# BUOI13.net
KiCad netlist of a schematic drawn in Altium Designer
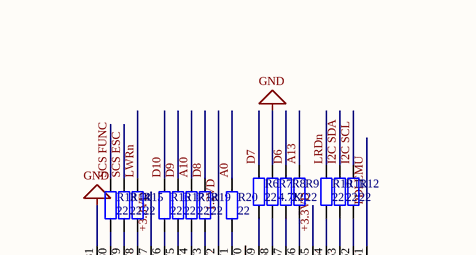
[diagram p0: BUOI13.SchDoc, top left]
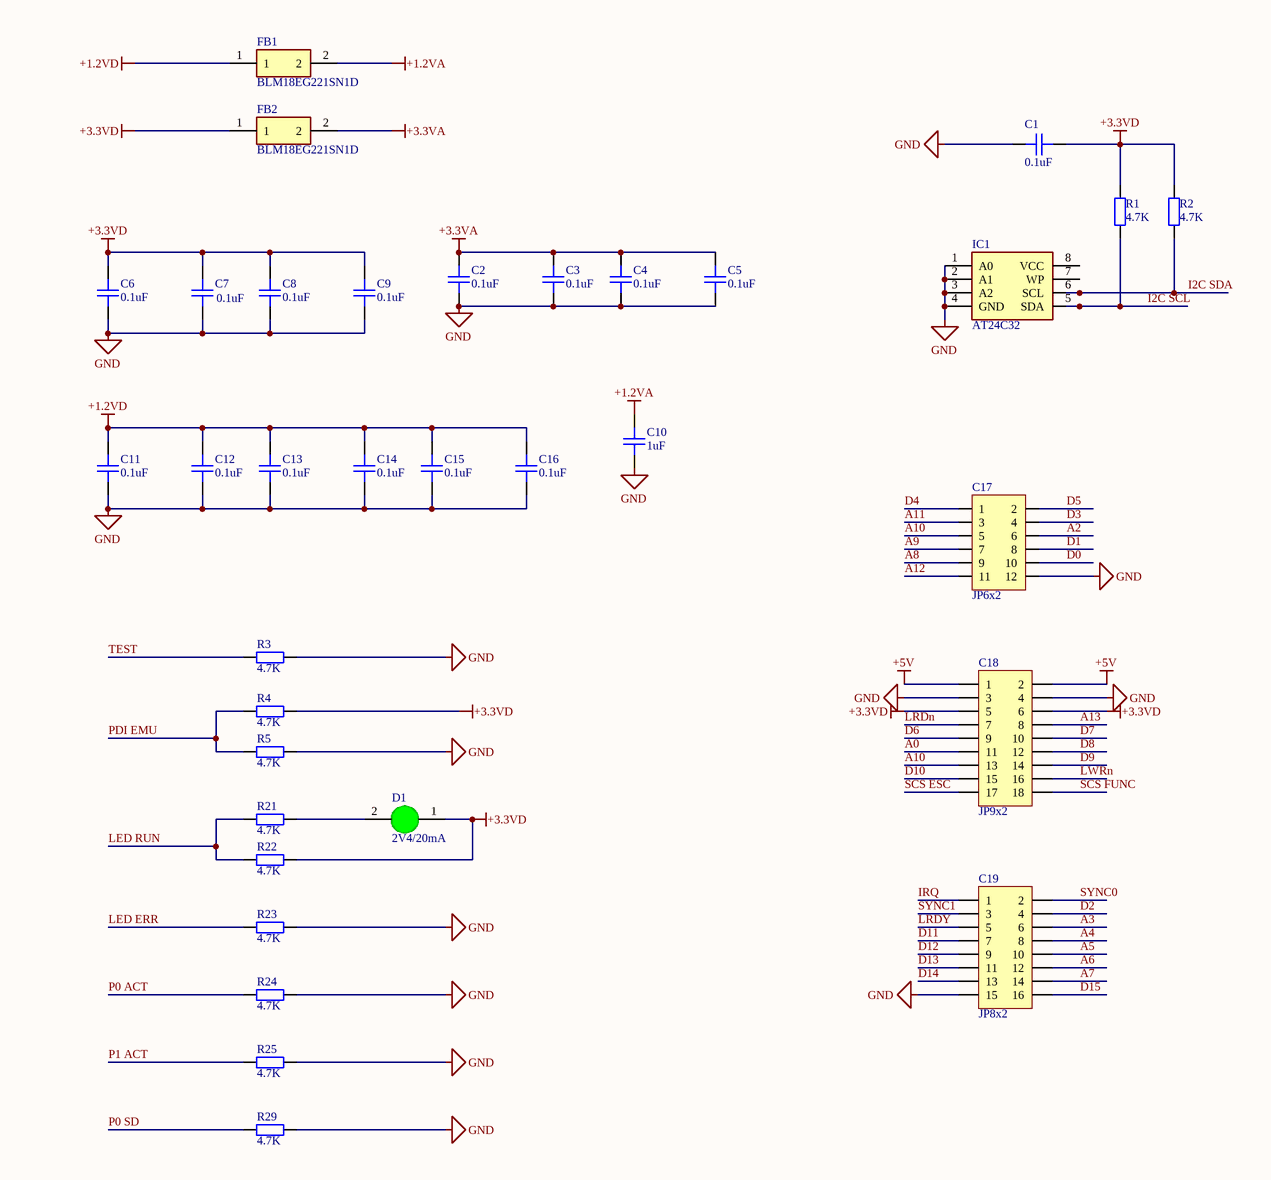
[diagram p1: BUOI13.SchDoc, top right]
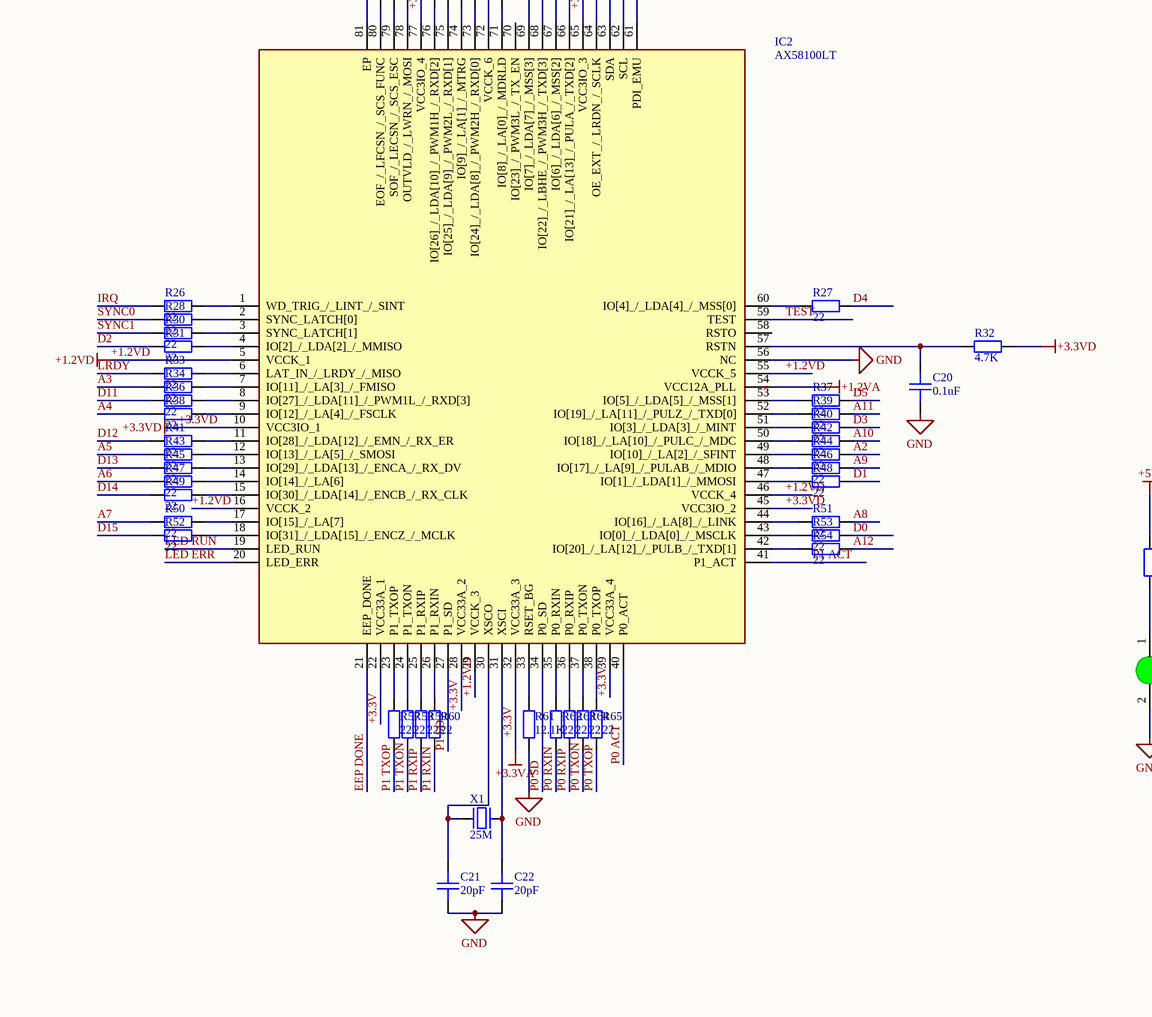
[diagram p2: BUOI13.SchDoc, bottom left]
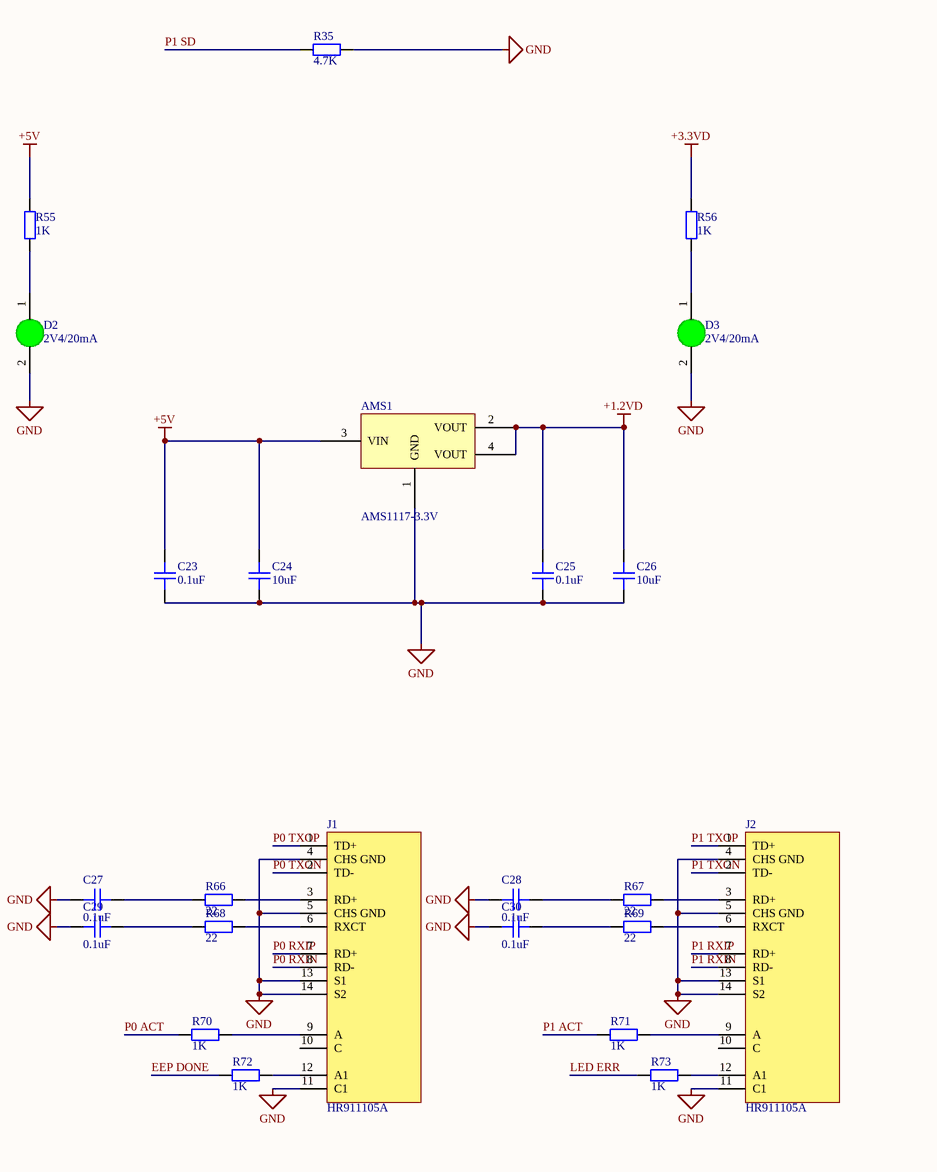
[diagram p3: BUOI13.SchDoc, bottom right]

(export (version "E")
  (design (tool "Eeschema 10.0.6"))
  (components
    (comp (ref "AMS1")
      (value "AMS1117-3.3V")
      (footprint "SOT223-4N")
      (description "Dán")
      (libsource (lib "THU VIEN SCH") (part "AMS1117"))
    )
    (comp (ref "C1")
      (value "0.1uF")
      (footprint "CAPC-0603 (1608)")
      (description "CAP CER 33pF 50V 5%  0603")
      (fields (field (name "MPN") "CL10C330JB8NNNC, 0603N330J500CT"))
      (libsource (lib "BYTECH_HW_LIB_2019 (1)") (part "0603N330J500CT"))
    )
    (comp (ref "C2")
      (value "0.1uF")
      (footprint "CAPC-0603 (1608)")
      (description "CAP CER 33pF 50V 5%  0603")
      (fields (field (name "MPN") "CL10C330JB8NNNC, 0603N330J500CT"))
      (libsource (lib "BYTECH_HW_LIB_2019 (1)") (part "0603N330J500CT"))
    )
    (comp (ref "C3")
      (value "0.1uF")
      (footprint "CAPC-0603 (1608)")
      (description "CAP CER 33pF 50V 5%  0603")
      (fields (field (name "MPN") "CL10C330JB8NNNC, 0603N330J500CT"))
      (libsource (lib "BYTECH_HW_LIB_2019 (1)") (part "0603N330J500CT"))
    )
    (comp (ref "C4")
      (value "0.1uF")
      (footprint "CAPC-0603 (1608)")
      (description "CAP CER 33pF 50V 5%  0603")
      (fields (field (name "MPN") "CL10C330JB8NNNC, 0603N330J500CT"))
      (libsource (lib "BYTECH_HW_LIB_2019 (1)") (part "0603N330J500CT"))
    )
    (comp (ref "C5")
      (value "0.1uF")
      (footprint "CAPC-0603 (1608)")
      (description "CAP CER 33pF 50V 5%  0603")
      (fields (field (name "MPN") "CL10C330JB8NNNC, 0603N330J500CT"))
      (libsource (lib "BYTECH_HW_LIB_2019 (1)") (part "0603N330J500CT"))
    )
    (comp (ref "C6")
      (value "0.1uF")
      (footprint "CAPC-0603 (1608)")
      (description "CAP CER 33pF 50V 5%  0603")
      (fields (field (name "MPN") "CL10C330JB8NNNC, 0603N330J500CT"))
      (libsource (lib "BYTECH_HW_LIB_2019 (1)") (part "0603N330J500CT"))
    )
    (comp (ref "C7")
      (value "0.1uF")
      (footprint "CAPC-0603 (1608)")
      (description "CAP CER 33pF 50V 5%  0603")
      (fields (field (name "MPN") "CL10C330JB8NNNC, 0603N330J500CT"))
      (libsource (lib "BYTECH_HW_LIB_2019 (1)") (part "0603N330J500CT"))
    )
    (comp (ref "C8")
      (value "0.1uF")
      (footprint "CAPC-0603 (1608)")
      (description "CAP CER 33pF 50V 5%  0603")
      (fields (field (name "MPN") "CL10C330JB8NNNC, 0603N330J500CT"))
      (libsource (lib "BYTECH_HW_LIB_2019 (1)") (part "0603N330J500CT"))
    )
    (comp (ref "C9")
      (value "0.1uF")
      (footprint "CAPC-0603 (1608)")
      (description "CAP CER 33pF 50V 5%  0603")
      (fields (field (name "MPN") "CL10C330JB8NNNC, 0603N330J500CT"))
      (libsource (lib "BYTECH_HW_LIB_2019 (1)") (part "0603N330J500CT"))
    )
    (comp (ref "C10")
      (value "1uF")
      (footprint "CAPC-0603 (1608)")
      (description "CAP CER 33pF 50V 5%  0603")
      (fields (field (name "MPN") "CL10C330JB8NNNC, 0603N330J500CT"))
      (libsource (lib "BYTECH_HW_LIB_2019 (1)") (part "0603N330J500CT"))
    )
    (comp (ref "C11")
      (value "0.1uF")
      (footprint "CAPC-0603 (1608)")
      (description "CAP CER 33pF 50V 5%  0603")
      (fields (field (name "MPN") "CL10C330JB8NNNC, 0603N330J500CT"))
      (libsource (lib "BYTECH_HW_LIB_2019 (1)") (part "0603N330J500CT"))
    )
    (comp (ref "C12")
      (value "0.1uF")
      (footprint "CAPC-0603 (1608)")
      (description "CAP CER 33pF 50V 5%  0603")
      (fields (field (name "MPN") "CL10C330JB8NNNC, 0603N330J500CT"))
      (libsource (lib "BYTECH_HW_LIB_2019 (1)") (part "0603N330J500CT"))
    )
    (comp (ref "C13")
      (value "0.1uF")
      (footprint "CAPC-0603 (1608)")
      (description "CAP CER 33pF 50V 5%  0603")
      (fields (field (name "MPN") "CL10C330JB8NNNC, 0603N330J500CT"))
      (libsource (lib "BYTECH_HW_LIB_2019 (1)") (part "0603N330J500CT"))
    )
    (comp (ref "C14")
      (value "0.1uF")
      (footprint "CAPC-0603 (1608)")
      (description "CAP CER 33pF 50V 5%  0603")
      (fields (field (name "MPN") "CL10C330JB8NNNC, 0603N330J500CT"))
      (libsource (lib "BYTECH_HW_LIB_2019 (1)") (part "0603N330J500CT"))
    )
    (comp (ref "C15")
      (value "0.1uF")
      (footprint "CAPC-0603 (1608)")
      (description "CAP CER 33pF 50V 5%  0603")
      (fields (field (name "MPN") "CL10C330JB8NNNC, 0603N330J500CT"))
      (libsource (lib "BYTECH_HW_LIB_2019 (1)") (part "0603N330J500CT"))
    )
    (comp (ref "C16")
      (value "0.1uF")
      (footprint "CAPC-0603 (1608)")
      (description "CAP CER 33pF 50V 5%  0603")
      (fields (field (name "MPN") "CL10C330JB8NNNC, 0603N330J500CT"))
      (libsource (lib "BYTECH_HW_LIB_2019 (1)") (part "0603N330J500CT"))
    )
    (comp (ref "C17")
      (value "JP6x2")
      (footprint "JP6-D2T")
      (description "WR-PHD 2.54 mm Dual Socket Header")
      (fields
        (field (name "MANUFACTURER") "Würth Elektronik eiSos GmbH")
        (field (name "PARTNO") "61301221821")
        (field (name "CREATED BY") "Karrer Zheng")
      )
      (libsource (lib "TechMT.VN_Lib_Project v2") (part "JP6x2"))
    )
    (comp (ref "C18")
      (value "JP9x2")
      (footprint "JP9-D2T")
      (description "WR-PHD 2.54 mm Dual Socket Header")
      (fields
        (field (name "MANUFACTURER") "Würth Elektronik eiSos GmbH")
        (field (name "PARTNO") "61301821821")
        (field (name "CREATED BY") "Karrer Zheng")
      )
      (libsource (lib "TechMT.VN_Lib_Project v2") (part "JP9x2"))
    )
    (comp (ref "C19")
      (value "JP8x2")
      (footprint "JP8-D2T")
      (description "WR-PHD 2.54 mm Dual Socket Header")
      (fields
        (field (name "MANUFACTURER") "Würth Elektronik eiSos GmbH")
        (field (name "PARTNO") "61301621821")
        (field (name "CREATED BY") "Karrer Zheng")
      )
      (libsource (lib "TechMT.VN_Lib_Project v2") (part "JP8x2"))
    )
    (comp (ref "C20")
      (value "0.1uF")
      (footprint "CAPC-0603 (1608)")
      (description "CAP CER 33pF 50V 5%  0603")
      (fields (field (name "MPN") "CL10C330JB8NNNC, 0603N330J500CT"))
      (libsource (lib "BYTECH_HW_LIB_2019 (1)") (part "0603N330J500CT"))
    )
    (comp (ref "C21")
      (value "20pF")
      (footprint "CAPC-0603 (1608)")
      (description "CAP CER 33pF 50V 5%  0603")
      (fields (field (name "MPN") "CL10C330JB8NNNC, 0603N330J500CT"))
      (libsource (lib "BYTECH_HW_LIB_2019 (1)") (part "0603N330J500CT"))
    )
    (comp (ref "C22")
      (value "20pF")
      (footprint "CAPC-0603 (1608)")
      (description "CAP CER 33pF 50V 5%  0603")
      (fields (field (name "MPN") "CL10C330JB8NNNC, 0603N330J500CT"))
      (libsource (lib "BYTECH_HW_LIB_2019 (1)") (part "0603N330J500CT"))
    )
    (comp (ref "C23")
      (value "0.1uF")
      (footprint "CAPC-0603 (1608)")
      (description "CAP CER 33pF 50V 5%  0603")
      (fields (field (name "MPN") "CL10C330JB8NNNC, 0603N330J500CT"))
      (libsource (lib "BYTECH_HW_LIB_2019 (1)") (part "0603N330J500CT"))
    )
    (comp (ref "C24")
      (value "10uF")
      (footprint "CAPC-0603 (1608)")
      (description "CAP CER 33pF 50V 5%  0603")
      (fields (field (name "MPN") "CL10C330JB8NNNC, 0603N330J500CT"))
      (libsource (lib "BYTECH_HW_LIB_2019 (1)") (part "0603N330J500CT"))
    )
    (comp (ref "C25")
      (value "0.1uF")
      (footprint "CAPC-0603 (1608)")
      (description "CAP CER 33pF 50V 5%  0603")
      (fields (field (name "MPN") "CL10C330JB8NNNC, 0603N330J500CT"))
      (libsource (lib "BYTECH_HW_LIB_2019 (1)") (part "0603N330J500CT"))
    )
    (comp (ref "C26")
      (value "10uF")
      (footprint "CAPC-0603 (1608)")
      (description "CAP CER 33pF 50V 5%  0603")
      (fields (field (name "MPN") "CL10C330JB8NNNC, 0603N330J500CT"))
      (libsource (lib "BYTECH_HW_LIB_2019 (1)") (part "0603N330J500CT"))
    )
    (comp (ref "C27")
      (value "0.1uF")
      (footprint "CAPC-0603 (1608)")
      (description "CAP CER 33pF 50V 5%  0603")
      (fields (field (name "MPN") "CL10C330JB8NNNC, 0603N330J500CT"))
      (libsource (lib "BYTECH_HW_LIB_2019 (1)") (part "0603N330J500CT"))
    )
    (comp (ref "C28")
      (value "0.1uF")
      (footprint "CAPC-0603 (1608)")
      (description "CAP CER 33pF 50V 5%  0603")
      (fields (field (name "MPN") "CL10C330JB8NNNC, 0603N330J500CT"))
      (libsource (lib "BYTECH_HW_LIB_2019 (1)") (part "0603N330J500CT"))
    )
    (comp (ref "C29")
      (value "0.1uF")
      (footprint "CAPC-0603 (1608)")
      (description "CAP CER 33pF 50V 5%  0603")
      (fields (field (name "MPN") "CL10C330JB8NNNC, 0603N330J500CT"))
      (libsource (lib "BYTECH_HW_LIB_2019 (1)") (part "0603N330J500CT"))
    )
    (comp (ref "C30")
      (value "0.1uF")
      (footprint "CAPC-0603 (1608)")
      (description "CAP CER 33pF 50V 5%  0603")
      (fields (field (name "MPN") "CL10C330JB8NNNC, 0603N330J500CT"))
      (libsource (lib "BYTECH_HW_LIB_2019 (1)") (part "0603N330J500CT"))
    )
    (comp (ref "D1")
      (value "2V4/20mA")
      (footprint "LED_0805_GREEN")
      (description "LED GREEN CLEAR 2V4 20mA 0805 SMD")
      (fields (field (name "MPN") "17-21/G6C-FM1N2B/3T"))
      (libsource (lib "BYTECH_HW_LIB_2019 (1)") (part "17-21/G6C-FM1N2B/3T"))
    )
    (comp (ref "D2")
      (value "2V4/20mA")
      (footprint "LED_0805_GREEN")
      (description "LED GREEN CLEAR 2V4 20mA 0805 SMD")
      (fields (field (name "MPN") "17-21/G6C-FM1N2B/3T"))
      (libsource (lib "BYTECH_HW_LIB_2019 (1)") (part "17-21/G6C-FM1N2B/3T"))
    )
    (comp (ref "D3")
      (value "2V4/20mA")
      (footprint "LED_0805_GREEN")
      (description "LED GREEN CLEAR 2V4 20mA 0805 SMD")
      (fields (field (name "MPN") "17-21/G6C-FM1N2B/3T"))
      (libsource (lib "BYTECH_HW_LIB_2019 (1)") (part "17-21/G6C-FM1N2B/3T"))
    )
    (comp (ref "FB1")
      (value "BLM18EG221SN1D")
      (footprint "BLM18EG121SH1D")
      (description "Ferrite Bead")
      (fields (field (name "MOUSER PART NUMBER") "81-BLM18EG221SN1D"))
      (libsource (lib "BLM") (part "BLM18EG221SN1D"))
    )
    (comp (ref "FB2")
      (value "BLM18EG221SN1D")
      (footprint "BLM18EG121SH1D")
      (description "Ferrite Bead")
      (fields (field (name "MOUSER PART NUMBER") "81-BLM18EG221SN1D"))
      (libsource (lib "BLM") (part "BLM18EG221SN1D"))
    )
    (comp (ref "IC1")
      (value "AT24C32")
      (footprint "SOIC127P600X175-8N")
      (description "Integrated Circuit")
      (libsource (lib "SamacSys") (part "AT24C32"))
    )
    (comp (ref "IC2")
      (value "AX58100LT")
      (footprint "QFP40P1200X1200X160-81N")
      (description "Integrated Circuit")
      (libsource (lib "BLM") (part "AX58100LT"))
    )
    (comp (ref "J1")
      (value "HR911105A")
      (footprint "HR911105A")
      (description "Hanrun HR911105A RJ-45 Connector")
      (fields (field (name "MFR") "HanRun"))
      (libsource (lib "BYTECH_HW_LIB_2019 (1)") (part "HR911105A"))
    )
    (comp (ref "J2")
      (value "HR911105A")
      (footprint "HR911105A")
      (description "Hanrun HR911105A RJ-45 Connector")
      (fields (field (name "MFR") "HanRun"))
      (libsource (lib "BYTECH_HW_LIB_2019 (1)") (part "HR911105A"))
    )
    (comp (ref "R1")
      (value "4.7K")
      (footprint "RESC-0603 (1608)")
      (description "RES SMD 13K OHM 1% 1/10W 0603")
      (fields (field (name "MPN") "AC0603FR-0713KL"))
      (libsource (lib "") (part "AC0603FR-0713KL_2"))
    )
    (comp (ref "R2")
      (value "4.7K")
      (footprint "RESC-0603 (1608)")
      (description "RES SMD 13K OHM 1% 1/10W 0603")
      (fields (field (name "MPN") "AC0603FR-0713KL"))
      (libsource (lib "") (part "AC0603FR-0713KL_2"))
    )
    (comp (ref "R3")
      (value "4.7K")
      (footprint "RESC-0603 (1608)")
      (description "RES SMD 13K OHM 1% 1/10W 0603")
      (fields (field (name "MPN") "AC0603FR-0713KL"))
      (libsource (lib "") (part "AC0603FR-0713KL_3"))
    )
    (comp (ref "R4")
      (value "4.7K")
      (footprint "RESC-0603 (1608)")
      (description "RES SMD 13K OHM 1% 1/10W 0603")
      (fields (field (name "MPN") "AC0603FR-0713KL"))
      (libsource (lib "") (part "AC0603FR-0713KL_3"))
    )
    (comp (ref "R5")
      (value "4.7K")
      (footprint "RESC-0603 (1608)")
      (description "RES SMD 13K OHM 1% 1/10W 0603")
      (fields (field (name "MPN") "AC0603FR-0713KL"))
      (libsource (lib "") (part "AC0603FR-0713KL_3"))
    )
    (comp (ref "R6")
      (value "22")
      (footprint "RESC-0603 (1608)")
      (description "RES SMD 13K OHM 1% 1/10W 0603")
      (fields (field (name "MPN") "AC0603FR-0713KL"))
      (libsource (lib "") (part "AC0603FR-0713KL_2"))
    )
    (comp (ref "R7")
      (value "4.7K")
      (footprint "RESC-0603 (1608)")
      (description "RES SMD 13K OHM 1% 1/10W 0603")
      (fields (field (name "MPN") "AC0603FR-0713KL"))
      (libsource (lib "") (part "AC0603FR-0713KL_2"))
    )
    (comp (ref "R8")
      (value "22")
      (footprint "RESC-0603 (1608)")
      (description "RES SMD 13K OHM 1% 1/10W 0603")
      (fields (field (name "MPN") "AC0603FR-0713KL"))
      (libsource (lib "") (part "AC0603FR-0713KL_2"))
    )
    (comp (ref "R9")
      (value "22")
      (footprint "RESC-0603 (1608)")
      (description "RES SMD 13K OHM 1% 1/10W 0603")
      (fields (field (name "MPN") "AC0603FR-0713KL"))
      (libsource (lib "BYTECH_HW_LIB_2019 (1)") (part "AC0603FR-0713KL"))
    )
    (comp (ref "R10")
      (value "22")
      (footprint "RESC-0603 (1608)")
      (description "RES SMD 13K OHM 1% 1/10W 0603")
      (fields (field (name "MPN") "AC0603FR-0713KL"))
      (libsource (lib "BYTECH_HW_LIB_2019 (1)") (part "AC0603FR-0713KL"))
    )
    (comp (ref "R11")
      (value "22")
      (footprint "RESC-0603 (1608)")
      (description "RES SMD 13K OHM 1% 1/10W 0603")
      (fields (field (name "MPN") "AC0603FR-0713KL"))
      (libsource (lib "BYTECH_HW_LIB_2019 (1)") (part "AC0603FR-0713KL"))
    )
    (comp (ref "R12")
      (value "22")
      (footprint "RESC-0603 (1608)")
      (description "RES SMD 13K OHM 1% 1/10W 0603")
      (fields (field (name "MPN") "AC0603FR-0713KL"))
      (libsource (lib "BYTECH_HW_LIB_2019 (1)") (part "AC0603FR-0713KL"))
    )
    (comp (ref "R13")
      (value "22")
      (footprint "RESC-0603 (1608)")
      (description "RES SMD 13K OHM 1% 1/10W 0603")
      (fields (field (name "MPN") "AC0603FR-0713KL"))
      (libsource (lib "BYTECH_HW_LIB_2019 (1)") (part "AC0603FR-0713KL"))
    )
    (comp (ref "R14")
      (value "22")
      (footprint "RESC-0603 (1608)")
      (description "RES SMD 13K OHM 1% 1/10W 0603")
      (fields (field (name "MPN") "AC0603FR-0713KL"))
      (libsource (lib "BYTECH_HW_LIB_2019 (1)") (part "AC0603FR-0713KL"))
    )
    (comp (ref "R15")
      (value "22")
      (footprint "RESC-0603 (1608)")
      (description "RES SMD 13K OHM 1% 1/10W 0603")
      (fields (field (name "MPN") "AC0603FR-0713KL"))
      (libsource (lib "BYTECH_HW_LIB_2019 (1)") (part "AC0603FR-0713KL"))
    )
    (comp (ref "R16")
      (value "22")
      (footprint "RESC-0603 (1608)")
      (description "RES SMD 13K OHM 1% 1/10W 0603")
      (fields (field (name "MPN") "AC0603FR-0713KL"))
      (libsource (lib "BYTECH_HW_LIB_2019 (1)") (part "AC0603FR-0713KL"))
    )
    (comp (ref "R17")
      (value "22")
      (footprint "RESC-0603 (1608)")
      (description "RES SMD 13K OHM 1% 1/10W 0603")
      (fields (field (name "MPN") "AC0603FR-0713KL"))
      (libsource (lib "BYTECH_HW_LIB_2019 (1)") (part "AC0603FR-0713KL"))
    )
    (comp (ref "R18")
      (value "22")
      (footprint "RESC-0603 (1608)")
      (description "RES SMD 13K OHM 1% 1/10W 0603")
      (fields (field (name "MPN") "AC0603FR-0713KL"))
      (libsource (lib "") (part "AC0603FR-0713KL_2"))
    )
    (comp (ref "R19")
      (value "22")
      (footprint "RESC-0603 (1608)")
      (description "RES SMD 13K OHM 1% 1/10W 0603")
      (fields (field (name "MPN") "AC0603FR-0713KL"))
      (libsource (lib "BYTECH_HW_LIB_2019 (1)") (part "AC0603FR-0713KL"))
    )
    (comp (ref "R20")
      (value "22")
      (footprint "RESC-0603 (1608)")
      (description "RES SMD 13K OHM 1% 1/10W 0603")
      (fields (field (name "MPN") "AC0603FR-0713KL"))
      (libsource (lib "") (part "AC0603FR-0713KL_2"))
    )
    (comp (ref "R21")
      (value "4.7K")
      (footprint "RESC-0603 (1608)")
      (description "RES SMD 13K OHM 1% 1/10W 0603")
      (fields (field (name "MPN") "AC0603FR-0713KL"))
      (libsource (lib "") (part "AC0603FR-0713KL_3"))
    )
    (comp (ref "R22")
      (value "4.7K")
      (footprint "RESC-0603 (1608)")
      (description "RES SMD 13K OHM 1% 1/10W 0603")
      (fields (field (name "MPN") "AC0603FR-0713KL"))
      (libsource (lib "") (part "AC0603FR-0713KL_3"))
    )
    (comp (ref "R23")
      (value "4.7K")
      (footprint "RESC-0603 (1608)")
      (description "RES SMD 13K OHM 1% 1/10W 0603")
      (fields (field (name "MPN") "AC0603FR-0713KL"))
      (libsource (lib "") (part "AC0603FR-0713KL_3"))
    )
    (comp (ref "R24")
      (value "4.7K")
      (footprint "RESC-0603 (1608)")
      (description "RES SMD 13K OHM 1% 1/10W 0603")
      (fields (field (name "MPN") "AC0603FR-0713KL"))
      (libsource (lib "") (part "AC0603FR-0713KL_3"))
    )
    (comp (ref "R25")
      (value "4.7K")
      (footprint "RESC-0603 (1608)")
      (description "RES SMD 13K OHM 1% 1/10W 0603")
      (fields (field (name "MPN") "AC0603FR-0713KL"))
      (libsource (lib "") (part "AC0603FR-0713KL_3"))
    )
    (comp (ref "R26")
      (value "22")
      (footprint "RESC-0603 (1608)")
      (description "RES SMD 13K OHM 1% 1/10W 0603")
      (fields (field (name "MPN") "AC0603FR-0713KL"))
      (libsource (lib "") (part "AC0603FR-0713KL_1"))
    )
    (comp (ref "R27")
      (value "22")
      (footprint "RESC-0603 (1608)")
      (description "RES SMD 13K OHM 1% 1/10W 0603")
      (fields (field (name "MPN") "AC0603FR-0713KL"))
      (libsource (lib "") (part "AC0603FR-0713KL_1"))
    )
    (comp (ref "R28")
      (value "22")
      (footprint "RESC-0603 (1608)")
      (description "RES SMD 13K OHM 1% 1/10W 0603")
      (fields (field (name "MPN") "AC0603FR-0713KL"))
      (libsource (lib "") (part "AC0603FR-0713KL_1"))
    )
    (comp (ref "R29")
      (value "4.7K")
      (footprint "RESC-0603 (1608)")
      (description "RES SMD 13K OHM 1% 1/10W 0603")
      (fields (field (name "MPN") "AC0603FR-0713KL"))
      (libsource (lib "") (part "AC0603FR-0713KL_3"))
    )
    (comp (ref "R30")
      (value "22")
      (footprint "RESC-0603 (1608)")
      (description "RES SMD 13K OHM 1% 1/10W 0603")
      (fields (field (name "MPN") "AC0603FR-0713KL"))
      (libsource (lib "") (part "AC0603FR-0713KL_1"))
    )
    (comp (ref "R31")
      (value "22")
      (footprint "RESC-0603 (1608)")
      (description "RES SMD 13K OHM 1% 1/10W 0603")
      (fields (field (name "MPN") "AC0603FR-0713KL"))
      (libsource (lib "") (part "AC0603FR-0713KL_1"))
    )
    (comp (ref "R32")
      (value "4.7K")
      (footprint "RESC-0603 (1608)")
      (description "RES SMD 13K OHM 1% 1/10W 0603")
      (fields (field (name "MPN") "AC0603FR-0713KL"))
      (libsource (lib "") (part "AC0603FR-0713KL_1"))
    )
    (comp (ref "R33")
      (value "22")
      (footprint "RESC-0603 (1608)")
      (description "RES SMD 13K OHM 1% 1/10W 0603")
      (fields (field (name "MPN") "AC0603FR-0713KL"))
      (libsource (lib "") (part "AC0603FR-0713KL_1"))
    )
    (comp (ref "R34")
      (value "22")
      (footprint "RESC-0603 (1608)")
      (description "RES SMD 13K OHM 1% 1/10W 0603")
      (fields (field (name "MPN") "AC0603FR-0713KL"))
      (libsource (lib "") (part "AC0603FR-0713KL_1"))
    )
    (comp (ref "R35")
      (value "4.7K")
      (footprint "RESC-0603 (1608)")
      (description "RES SMD 13K OHM 1% 1/10W 0603")
      (fields (field (name "MPN") "AC0603FR-0713KL"))
      (libsource (lib "") (part "AC0603FR-0713KL_3"))
    )
    (comp (ref "R36")
      (value "22")
      (footprint "RESC-0603 (1608)")
      (description "RES SMD 13K OHM 1% 1/10W 0603")
      (fields (field (name "MPN") "AC0603FR-0713KL"))
      (libsource (lib "") (part "AC0603FR-0713KL_1"))
    )
    (comp (ref "R37")
      (value "22")
      (footprint "RESC-0603 (1608)")
      (description "RES SMD 13K OHM 1% 1/10W 0603")
      (fields (field (name "MPN") "AC0603FR-0713KL"))
      (libsource (lib "") (part "AC0603FR-0713KL_1"))
    )
    (comp (ref "R38")
      (value "22")
      (footprint "RESC-0603 (1608)")
      (description "RES SMD 13K OHM 1% 1/10W 0603")
      (fields (field (name "MPN") "AC0603FR-0713KL"))
      (libsource (lib "") (part "AC0603FR-0713KL_1"))
    )
    (comp (ref "R39")
      (value "22")
      (footprint "RESC-0603 (1608)")
      (description "RES SMD 13K OHM 1% 1/10W 0603")
      (fields (field (name "MPN") "AC0603FR-0713KL"))
      (libsource (lib "") (part "AC0603FR-0713KL_1"))
    )
    (comp (ref "R40")
      (value "22")
      (footprint "RESC-0603 (1608)")
      (description "RES SMD 13K OHM 1% 1/10W 0603")
      (fields (field (name "MPN") "AC0603FR-0713KL"))
      (libsource (lib "") (part "AC0603FR-0713KL_1"))
    )
    (comp (ref "R41")
      (value "22")
      (footprint "RESC-0603 (1608)")
      (description "RES SMD 13K OHM 1% 1/10W 0603")
      (fields (field (name "MPN") "AC0603FR-0713KL"))
      (libsource (lib "") (part "AC0603FR-0713KL_1"))
    )
    (comp (ref "R42")
      (value "22")
      (footprint "RESC-0603 (1608)")
      (description "RES SMD 13K OHM 1% 1/10W 0603")
      (fields (field (name "MPN") "AC0603FR-0713KL"))
      (libsource (lib "") (part "AC0603FR-0713KL_1"))
    )
    (comp (ref "R43")
      (value "22")
      (footprint "RESC-0603 (1608)")
      (description "RES SMD 13K OHM 1% 1/10W 0603")
      (fields (field (name "MPN") "AC0603FR-0713KL"))
      (libsource (lib "") (part "AC0603FR-0713KL_1"))
    )
    (comp (ref "R44")
      (value "22")
      (footprint "RESC-0603 (1608)")
      (description "RES SMD 13K OHM 1% 1/10W 0603")
      (fields (field (name "MPN") "AC0603FR-0713KL"))
      (libsource (lib "") (part "AC0603FR-0713KL_1"))
    )
    (comp (ref "R45")
      (value "22")
      (footprint "RESC-0603 (1608)")
      (description "RES SMD 13K OHM 1% 1/10W 0603")
      (fields (field (name "MPN") "AC0603FR-0713KL"))
      (libsource (lib "") (part "AC0603FR-0713KL_1"))
    )
    (comp (ref "R46")
      (value "22")
      (footprint "RESC-0603 (1608)")
      (description "RES SMD 13K OHM 1% 1/10W 0603")
      (fields (field (name "MPN") "AC0603FR-0713KL"))
      (libsource (lib "") (part "AC0603FR-0713KL_1"))
    )
    (comp (ref "R47")
      (value "22")
      (footprint "RESC-0603 (1608)")
      (description "RES SMD 13K OHM 1% 1/10W 0603")
      (fields (field (name "MPN") "AC0603FR-0713KL"))
      (libsource (lib "") (part "AC0603FR-0713KL_1"))
    )
    (comp (ref "R48")
      (value "22")
      (footprint "RESC-0603 (1608)")
      (description "RES SMD 13K OHM 1% 1/10W 0603")
      (fields (field (name "MPN") "AC0603FR-0713KL"))
      (libsource (lib "") (part "AC0603FR-0713KL_1"))
    )
    (comp (ref "R49")
      (value "22")
      (footprint "RESC-0603 (1608)")
      (description "RES SMD 13K OHM 1% 1/10W 0603")
      (fields (field (name "MPN") "AC0603FR-0713KL"))
      (libsource (lib "") (part "AC0603FR-0713KL_1"))
    )
    (comp (ref "R50")
      (value "22")
      (footprint "RESC-0603 (1608)")
      (description "RES SMD 13K OHM 1% 1/10W 0603")
      (fields (field (name "MPN") "AC0603FR-0713KL"))
      (libsource (lib "") (part "AC0603FR-0713KL_1"))
    )
    (comp (ref "R51")
      (value "22")
      (footprint "RESC-0603 (1608)")
      (description "RES SMD 13K OHM 1% 1/10W 0603")
      (fields (field (name "MPN") "AC0603FR-0713KL"))
      (libsource (lib "") (part "AC0603FR-0713KL_1"))
    )
    (comp (ref "R52")
      (value "22")
      (footprint "RESC-0603 (1608)")
      (description "RES SMD 13K OHM 1% 1/10W 0603")
      (fields (field (name "MPN") "AC0603FR-0713KL"))
      (libsource (lib "") (part "AC0603FR-0713KL_1"))
    )
    (comp (ref "R53")
      (value "22")
      (footprint "RESC-0603 (1608)")
      (description "RES SMD 13K OHM 1% 1/10W 0603")
      (fields (field (name "MPN") "AC0603FR-0713KL"))
      (libsource (lib "") (part "AC0603FR-0713KL_1"))
    )
    (comp (ref "R54")
      (value "22")
      (footprint "RESC-0603 (1608)")
      (description "RES SMD 13K OHM 1% 1/10W 0603")
      (fields (field (name "MPN") "AC0603FR-0713KL"))
      (libsource (lib "") (part "AC0603FR-0713KL_1"))
    )
    (comp (ref "R55")
      (value "1K")
      (footprint "RESC-0603 (1608)")
      (description "RES SMD 13K OHM 1% 1/10W 0603")
      (fields (field (name "MPN") "AC0603FR-0713KL"))
      (libsource (lib "") (part "AC0603FR-0713KL_2"))
    )
    (comp (ref "R56")
      (value "1K")
      (footprint "RESC-0603 (1608)")
      (description "RES SMD 13K OHM 1% 1/10W 0603")
      (fields (field (name "MPN") "AC0603FR-0713KL"))
      (libsource (lib "") (part "AC0603FR-0713KL_2"))
    )
    (comp (ref "R57")
      (value "22")
      (footprint "RESC-0603 (1608)")
      (description "RES SMD 13K OHM 1% 1/10W 0603")
      (fields (field (name "MPN") "AC0603FR-0713KL"))
      (libsource (lib "BYTECH_HW_LIB_2019 (1)") (part "AC0603FR-0713KL"))
    )
    (comp (ref "R58")
      (value "22")
      (footprint "RESC-0603 (1608)")
      (description "RES SMD 13K OHM 1% 1/10W 0603")
      (fields (field (name "MPN") "AC0603FR-0713KL"))
      (libsource (lib "BYTECH_HW_LIB_2019 (1)") (part "AC0603FR-0713KL"))
    )
    (comp (ref "R59")
      (value "22")
      (footprint "RESC-0603 (1608)")
      (description "RES SMD 13K OHM 1% 1/10W 0603")
      (fields (field (name "MPN") "AC0603FR-0713KL"))
      (libsource (lib "BYTECH_HW_LIB_2019 (1)") (part "AC0603FR-0713KL"))
    )
    (comp (ref "R60")
      (value "22")
      (footprint "RESC-0603 (1608)")
      (description "RES SMD 13K OHM 1% 1/10W 0603")
      (fields (field (name "MPN") "AC0603FR-0713KL"))
      (libsource (lib "BYTECH_HW_LIB_2019 (1)") (part "AC0603FR-0713KL"))
    )
    (comp (ref "R61")
      (value "12.1K")
      (footprint "RESC-0603 (1608)")
      (description "RES SMD 13K OHM 1% 1/10W 0603")
      (fields (field (name "MPN") "AC0603FR-0713KL"))
      (libsource (lib "BYTECH_HW_LIB_2019 (1)") (part "AC0603FR-0713KL"))
    )
    (comp (ref "R62")
      (value "22")
      (footprint "RESC-0603 (1608)")
      (description "RES SMD 13K OHM 1% 1/10W 0603")
      (fields (field (name "MPN") "AC0603FR-0713KL"))
      (libsource (lib "BYTECH_HW_LIB_2019 (1)") (part "AC0603FR-0713KL"))
    )
    (comp (ref "R63")
      (value "22")
      (footprint "RESC-0603 (1608)")
      (description "RES SMD 13K OHM 1% 1/10W 0603")
      (fields (field (name "MPN") "AC0603FR-0713KL"))
      (libsource (lib "BYTECH_HW_LIB_2019 (1)") (part "AC0603FR-0713KL"))
    )
    (comp (ref "R64")
      (value "22")
      (footprint "RESC-0603 (1608)")
      (description "RES SMD 13K OHM 1% 1/10W 0603")
      (fields (field (name "MPN") "AC0603FR-0713KL"))
      (libsource (lib "BYTECH_HW_LIB_2019 (1)") (part "AC0603FR-0713KL"))
    )
    (comp (ref "R65")
      (value "22")
      (footprint "RESC-0603 (1608)")
      (description "RES SMD 13K OHM 1% 1/10W 0603")
      (fields (field (name "MPN") "AC0603FR-0713KL"))
      (libsource (lib "BYTECH_HW_LIB_2019 (1)") (part "AC0603FR-0713KL"))
    )
    (comp (ref "R66")
      (value "22")
      (footprint "RESC-0603 (1608)")
      (description "RES SMD 13K OHM 1% 1/10W 0603")
      (fields (field (name "MPN") "AC0603FR-0713KL"))
      (libsource (lib "") (part "AC0603FR-0713KL_1"))
    )
    (comp (ref "R67")
      (value "22")
      (footprint "RESC-0603 (1608)")
      (description "RES SMD 13K OHM 1% 1/10W 0603")
      (fields (field (name "MPN") "AC0603FR-0713KL"))
      (libsource (lib "") (part "AC0603FR-0713KL_1"))
    )
    (comp (ref "R68")
      (value "22")
      (footprint "RESC-0603 (1608)")
      (description "RES SMD 13K OHM 1% 1/10W 0603")
      (fields (field (name "MPN") "AC0603FR-0713KL"))
      (libsource (lib "") (part "AC0603FR-0713KL_1"))
    )
    (comp (ref "R69")
      (value "22")
      (footprint "RESC-0603 (1608)")
      (description "RES SMD 13K OHM 1% 1/10W 0603")
      (fields (field (name "MPN") "AC0603FR-0713KL"))
      (libsource (lib "") (part "AC0603FR-0713KL_1"))
    )
    (comp (ref "R70")
      (value "1K")
      (footprint "RESC-0603 (1608)")
      (description "RES SMD 13K OHM 1% 1/10W 0603")
      (fields (field (name "MPN") "AC0603FR-0713KL"))
      (libsource (lib "") (part "AC0603FR-0713KL_1"))
    )
    (comp (ref "R71")
      (value "1K")
      (footprint "RESC-0603 (1608)")
      (description "RES SMD 13K OHM 1% 1/10W 0603")
      (fields (field (name "MPN") "AC0603FR-0713KL"))
      (libsource (lib "") (part "AC0603FR-0713KL_1"))
    )
    (comp (ref "R72")
      (value "1K")
      (footprint "RESC-0603 (1608)")
      (description "RES SMD 13K OHM 1% 1/10W 0603")
      (fields (field (name "MPN") "AC0603FR-0713KL"))
      (libsource (lib "") (part "AC0603FR-0713KL_1"))
    )
    (comp (ref "R73")
      (value "1K")
      (footprint "RESC-0603 (1608)")
      (description "RES SMD 13K OHM 1% 1/10W 0603")
      (fields (field (name "MPN") "AC0603FR-0713KL"))
      (libsource (lib "") (part "AC0603FR-0713KL_1"))
    )
    (comp (ref "X1")
      (value "25M")
      (footprint "XTAL-RU49/4")
      (description "Crystal, 32.768 KHz, -40 to 85 degC, 3.2 x 1.5 x 0.9 mm SMD")
      (libsource (lib "TechMT.VN_Lib_Project v2") (part "XT2"))
    )
  )
  (nets
    (net (code "1") (name "+1.2VA") (class "Default")
      (node (ref "C10") (pin "2") (pinfunction "2_2") (pintype "passive"))
      (node (ref "FB1") (pin "2") (pinfunction "2_2") (pintype "passive"))
      (node (ref "IC2") (pin "54") (pinfunction "VCC12A_PLL_54") (pintype "passive"))
    )
    (net (code "2") (name "+1.2VD") (class "Default")
      (node (ref "AMS1") (pin "2") (pinfunction "VOUT_2") (pintype "passive"))
      (node (ref "AMS1") (pin "4") (pinfunction "VOUT_4") (pintype "passive"))
      (node (ref "C11") (pin "2") (pinfunction "2_2") (pintype "passive"))
      (node (ref "C12") (pin "2") (pinfunction "2_2") (pintype "passive"))
      (node (ref "C13") (pin "2") (pinfunction "2_2") (pintype "passive"))
      (node (ref "C14") (pin "2") (pinfunction "2_2") (pintype "passive"))
      (node (ref "C15") (pin "2") (pinfunction "2_2") (pintype "passive"))
      (node (ref "C16") (pin "2") (pinfunction "2_2") (pintype "passive"))
      (node (ref "C25") (pin "2") (pinfunction "2_2") (pintype "passive"))
      (node (ref "C26") (pin "2") (pinfunction "2_2") (pintype "passive"))
      (node (ref "FB1") (pin "1") (pinfunction "1_1") (pintype "passive"))
      (node (ref "IC2") (pin "16") (pinfunction "VCCK_2_16") (pintype "passive"))
      (node (ref "IC2") (pin "29") (pinfunction "VCCK_3_29") (pintype "passive"))
      (node (ref "IC2") (pin "46") (pinfunction "VCCK_4_46") (pintype "passive"))
      (node (ref "IC2") (pin "5") (pinfunction "VCCK_1_5") (pintype "passive"))
      (node (ref "IC2") (pin "55") (pinfunction "VCCK_5_55") (pintype "passive"))
      (node (ref "IC2") (pin "72") (pinfunction "VCCK_6_72") (pintype "passive"))
    )
    (net (code "3") (name "+3.3VA") (class "Default")
      (node (ref "C2") (pin "2") (pinfunction "2_2") (pintype "passive"))
      (node (ref "C3") (pin "2") (pinfunction "2_2") (pintype "passive"))
      (node (ref "C4") (pin "2") (pinfunction "2_2") (pintype "passive"))
      (node (ref "C5") (pin "2") (pinfunction "2_2") (pintype "passive"))
      (node (ref "FB2") (pin "2") (pinfunction "2_2") (pintype "passive"))
      (node (ref "IC2") (pin "22") (pinfunction "VCC33A_1_22") (pintype "passive"))
      (node (ref "IC2") (pin "28") (pinfunction "VCC33A_2_28") (pintype "passive"))
      (node (ref "IC2") (pin "32") (pinfunction "VCC33A_3_32") (pintype "passive"))
      (node (ref "IC2") (pin "39") (pinfunction "VCC33A_4_39") (pintype "passive"))
    )
    (net (code "4") (name "+3.3VD") (class "Default")
      (node (ref "C1") (pin "1") (pinfunction "1_1") (pintype "passive"))
      (node (ref "C18") (pin "16") (pinfunction "6_16") (pintype "passive"))
      (node (ref "C18") (pin "3") (pinfunction "5_3") (pintype "passive"))
      (node (ref "C6") (pin "2") (pinfunction "2_2") (pintype "passive"))
      (node (ref "C7") (pin "2") (pinfunction "2_2") (pintype "passive"))
      (node (ref "C8") (pin "2") (pinfunction "2_2") (pintype "passive"))
      (node (ref "C9") (pin "2") (pinfunction "2_2") (pintype "passive"))
      (node (ref "D1") (pin "1") (pinfunction "A_1") (pintype "passive"))
      (node (ref "FB2") (pin "1") (pinfunction "1_1") (pintype "passive"))
      (node (ref "IC2") (pin "10") (pinfunction "VCC3IO_1_10") (pintype "passive"))
      (node (ref "IC2") (pin "45") (pinfunction "VCC3IO_2_45") (pintype "passive"))
      (node (ref "IC2") (pin "65") (pinfunction "VCC3IO_3_65") (pintype "passive"))
      (node (ref "IC2") (pin "77") (pinfunction "VCC3IO_4_77") (pintype "passive"))
      (node (ref "R1") (pin "2") (pinfunction "2_2") (pintype "passive"))
      (node (ref "R2") (pin "2") (pinfunction "2_2") (pintype "passive"))
      (node (ref "R22") (pin "1") (pinfunction "1_1") (pintype "passive"))
      (node (ref "R32") (pin "2") (pinfunction "2_2") (pintype "passive"))
      (node (ref "R4") (pin "1") (pinfunction "1_1") (pintype "passive"))
      (node (ref "R56") (pin "2") (pinfunction "2_2") (pintype "passive"))
    )
    (net (code "5") (name "+5V") (class "Default")
      (node (ref "AMS1") (pin "3") (pinfunction "VIN_3") (pintype "passive"))
      (node (ref "C18") (pin "1") (pinfunction "1_1") (pintype "passive"))
      (node (ref "C18") (pin "18") (pinfunction "2_18") (pintype "passive"))
      (node (ref "C23") (pin "2") (pinfunction "2_2") (pintype "passive"))
      (node (ref "C24") (pin "2") (pinfunction "2_2") (pintype "passive"))
      (node (ref "R55") (pin "2") (pinfunction "2_2") (pintype "passive"))
    )
    (net (code "6") (name "/A0") (class "Default")
      (node (ref "C18") (pin "6") (pinfunction "11_6") (pintype "passive"))
      (node (ref "R20") (pin "2") (pinfunction "2_2") (pintype "passive"))
    )
    (net (code "7") (name "/A2") (class "Default")
      (node (ref "C17") (pin "10") (pinfunction "6_10") (pintype "passive"))
      (node (ref "R44") (pin "2") (pinfunction "2_2") (pintype "passive"))
    )
    (net (code "8") (name "/A3") (class "Default")
      (node (ref "C19") (pin "14") (pinfunction "6_14") (pintype "passive"))
      (node (ref "R34") (pin "1") (pinfunction "1_1") (pintype "passive"))
    )
    (net (code "9") (name "/A4") (class "Default")
      (node (ref "C19") (pin "13") (pinfunction "8_13") (pintype "passive"))
      (node (ref "R38") (pin "1") (pinfunction "1_1") (pintype "passive"))
    )
    (net (code "10") (name "/A5") (class "Default")
      (node (ref "C19") (pin "12") (pinfunction "10_12") (pintype "passive"))
      (node (ref "R43") (pin "1") (pinfunction "1_1") (pintype "passive"))
    )
    (net (code "11") (name "/A6") (class "Default")
      (node (ref "C19") (pin "11") (pinfunction "12_11") (pintype "passive"))
      (node (ref "R47") (pin "1") (pinfunction "1_1") (pintype "passive"))
    )
    (net (code "12") (name "/A7") (class "Default")
      (node (ref "C19") (pin "10") (pinfunction "14_10") (pintype "passive"))
      (node (ref "R50") (pin "1") (pinfunction "1_1") (pintype "passive"))
    )
    (net (code "13") (name "/A8") (class "Default")
      (node (ref "C17") (pin "5") (pinfunction "9_5") (pintype "passive"))
      (node (ref "R51") (pin "2") (pinfunction "2_2") (pintype "passive"))
    )
    (net (code "14") (name "/A9") (class "Default")
      (node (ref "C17") (pin "4") (pinfunction "7_4") (pintype "passive"))
      (node (ref "R46") (pin "2") (pinfunction "2_2") (pintype "passive"))
    )
    (net (code "15") (name "/A10") (class "Default")
      (node (ref "C17") (pin "3") (pinfunction "5_3") (pintype "passive"))
      (node (ref "C18") (pin "7") (pinfunction "13_7") (pintype "passive"))
      (node (ref "R18") (pin "2") (pinfunction "2_2") (pintype "passive"))
      (node (ref "R42") (pin "2") (pinfunction "2_2") (pintype "passive"))
    )
    (net (code "16") (name "/A11") (class "Default")
      (node (ref "C17") (pin "2") (pinfunction "3_2") (pintype "passive"))
      (node (ref "R39") (pin "2") (pinfunction "2_2") (pintype "passive"))
    )
    (net (code "17") (name "/A12") (class "Default")
      (node (ref "C17") (pin "6") (pinfunction "11_6") (pintype "passive"))
      (node (ref "R54") (pin "2") (pinfunction "2_2") (pintype "passive"))
    )
    (net (code "18") (name "/A13") (class "Default")
      (node (ref "C18") (pin "15") (pinfunction "8_15") (pintype "passive"))
      (node (ref "R9") (pin "1") (pinfunction "1_1") (pintype "passive"))
    )
    (net (code "19") (name "/D0") (class "Default")
      (node (ref "C17") (pin "8") (pinfunction "10_8") (pintype "passive"))
      (node (ref "R53") (pin "2") (pinfunction "2_2") (pintype "passive"))
    )
    (net (code "20") (name "/D1") (class "Default")
      (node (ref "C17") (pin "9") (pinfunction "8_9") (pintype "passive"))
      (node (ref "R48") (pin "2") (pinfunction "2_2") (pintype "passive"))
    )
    (net (code "21") (name "/D2") (class "Default")
      (node (ref "C19") (pin "15") (pinfunction "4_15") (pintype "passive"))
      (node (ref "R31") (pin "1") (pinfunction "1_1") (pintype "passive"))
    )
    (net (code "22") (name "/D3") (class "Default")
      (node (ref "C17") (pin "11") (pinfunction "4_11") (pintype "passive"))
      (node (ref "R40") (pin "2") (pinfunction "2_2") (pintype "passive"))
    )
    (net (code "23") (name "/D4") (class "Default")
      (node (ref "C17") (pin "1") (pinfunction "1_1") (pintype "passive"))
      (node (ref "R27") (pin "2") (pinfunction "2_2") (pintype "passive"))
    )
    (net (code "24") (name "/D5") (class "Default")
      (node (ref "C17") (pin "12") (pinfunction "2_12") (pintype "passive"))
      (node (ref "R37") (pin "2") (pinfunction "2_2") (pintype "passive"))
    )
    (net (code "25") (name "/D6") (class "Default")
      (node (ref "C18") (pin "5") (pinfunction "9_5") (pintype "passive"))
      (node (ref "R8") (pin "2") (pinfunction "2_2") (pintype "passive"))
    )
    (net (code "26") (name "/D7") (class "Default")
      (node (ref "C18") (pin "14") (pinfunction "10_14") (pintype "passive"))
      (node (ref "R6") (pin "2") (pinfunction "2_2") (pintype "passive"))
    )
    (net (code "27") (name "/D8") (class "Default")
      (node (ref "C18") (pin "13") (pinfunction "12_13") (pintype "passive"))
      (node (ref "R19") (pin "1") (pinfunction "1_1") (pintype "passive"))
    )
    (net (code "28") (name "/D9") (class "Default")
      (node (ref "C18") (pin "12") (pinfunction "14_12") (pintype "passive"))
      (node (ref "R17") (pin "1") (pinfunction "1_1") (pintype "passive"))
    )
    (net (code "29") (name "/D10") (class "Default")
      (node (ref "C18") (pin "8") (pinfunction "15_8") (pintype "passive"))
      (node (ref "R16") (pin "1") (pinfunction "1_1") (pintype "passive"))
    )
    (net (code "30") (name "/D11") (class "Default")
      (node (ref "C19") (pin "4") (pinfunction "7_4") (pintype "passive"))
      (node (ref "R36") (pin "1") (pinfunction "1_1") (pintype "passive"))
    )
    (net (code "31") (name "/D12") (class "Default")
      (node (ref "C19") (pin "5") (pinfunction "9_5") (pintype "passive"))
      (node (ref "R41") (pin "1") (pinfunction "1_1") (pintype "passive"))
    )
    (net (code "32") (name "/D13") (class "Default")
      (node (ref "C19") (pin "6") (pinfunction "11_6") (pintype "passive"))
      (node (ref "R45") (pin "1") (pinfunction "1_1") (pintype "passive"))
    )
    (net (code "33") (name "/D14") (class "Default")
      (node (ref "C19") (pin "7") (pinfunction "13_7") (pintype "passive"))
      (node (ref "R49") (pin "1") (pinfunction "1_1") (pintype "passive"))
    )
    (net (code "34") (name "/D15") (class "Default")
      (node (ref "C19") (pin "9") (pinfunction "16_9") (pintype "passive"))
      (node (ref "R52") (pin "1") (pinfunction "1_1") (pintype "passive"))
    )
    (net (code "35") (name "/EEP DONE") (class "Default")
      (node (ref "IC2") (pin "21") (pinfunction "EEP_DONE_21") (pintype "passive"))
      (node (ref "R72") (pin "1") (pinfunction "1_1") (pintype "passive"))
    )
    (net (code "36") (name "/I2C SCL") (class "Default")
      (node (ref "IC1") (pin "5") (pinfunction "SDA_5") (pintype "passive"))
      (node (ref "R1") (pin "1") (pinfunction "1_1") (pintype "passive"))
      (node (ref "R12") (pin "1") (pinfunction "1_1") (pintype "passive"))
    )
    (net (code "37") (name "/I2C SDA") (class "Default")
      (node (ref "IC1") (pin "6") (pinfunction "SCL_6") (pintype "passive"))
      (node (ref "R11") (pin "1") (pinfunction "1_1") (pintype "passive"))
      (node (ref "R2") (pin "1") (pinfunction "1_1") (pintype "passive"))
    )
    (net (code "38") (name "/IRQ") (class "Default")
      (node (ref "C19") (pin "1") (pinfunction "1_1") (pintype "passive"))
      (node (ref "R26") (pin "1") (pinfunction "1_1") (pintype "passive"))
    )
    (net (code "39") (name "/LED ERR") (class "Default")
      (node (ref "IC2") (pin "20") (pinfunction "LED_ERR_20") (pintype "passive"))
      (node (ref "R23") (pin "2") (pinfunction "2_2") (pintype "passive"))
      (node (ref "R73") (pin "1") (pinfunction "1_1") (pintype "passive"))
    )
    (net (code "40") (name "/LED RUN") (class "Default")
      (node (ref "IC2") (pin "19") (pinfunction "LED_RUN_19") (pintype "passive"))
      (node (ref "R21") (pin "2") (pinfunction "2_2") (pintype "passive"))
      (node (ref "R22") (pin "2") (pinfunction "2_2") (pintype "passive"))
    )
    (net (code "41") (name "/LRDY") (class "Default")
      (node (ref "C19") (pin "3") (pinfunction "5_3") (pintype "passive"))
      (node (ref "R33") (pin "1") (pinfunction "1_1") (pintype "passive"))
    )
    (net (code "42") (name "/LRDn") (class "Default")
      (node (ref "C18") (pin "4") (pinfunction "7_4") (pintype "passive"))
      (node (ref "R10") (pin "1") (pinfunction "1_1") (pintype "passive"))
    )
    (net (code "43") (name "/LWRn") (class "Default")
      (node (ref "C18") (pin "11") (pinfunction "16_11") (pintype "passive"))
      (node (ref "R15") (pin "1") (pinfunction "1_1") (pintype "passive"))
    )
    (net (code "44") (name "/P0 ACT") (class "Default")
      (node (ref "IC2") (pin "40") (pinfunction "P0_ACT_40") (pintype "passive"))
      (node (ref "R24") (pin "2") (pinfunction "2_2") (pintype "passive"))
      (node (ref "R70") (pin "1") (pinfunction "1_1") (pintype "passive"))
    )
    (net (code "45") (name "/P0 RXIN") (class "Default")
      (node (ref "J1") (pin "8") (pinfunction "RD-_8") (pintype "passive"))
      (node (ref "R62") (pin "2") (pinfunction "2_2") (pintype "passive"))
    )
    (net (code "46") (name "/P0 RXIP") (class "Default")
      (node (ref "J1") (pin "7") (pinfunction "RD+_7") (pintype "passive"))
      (node (ref "R63") (pin "2") (pinfunction "2_2") (pintype "passive"))
    )
    (net (code "47") (name "/P0 SD") (class "Default")
      (node (ref "IC2") (pin "34") (pinfunction "P0_SD_34") (pintype "passive"))
      (node (ref "R29") (pin "2") (pinfunction "2_2") (pintype "passive"))
    )
    (net (code "48") (name "/P0 TXON") (class "Default")
      (node (ref "J1") (pin "2") (pinfunction "TD-_2") (pintype "passive"))
      (node (ref "R64") (pin "2") (pinfunction "2_2") (pintype "passive"))
    )
    (net (code "49") (name "/P0 TXOP") (class "Default")
      (node (ref "J1") (pin "1") (pinfunction "TD+_1") (pintype "passive"))
      (node (ref "R65") (pin "2") (pinfunction "2_2") (pintype "passive"))
    )
    (net (code "50") (name "/P1 ACT") (class "Default")
      (node (ref "IC2") (pin "41") (pinfunction "P1_ACT_41") (pintype "passive"))
      (node (ref "R25") (pin "2") (pinfunction "2_2") (pintype "passive"))
      (node (ref "R71") (pin "1") (pinfunction "1_1") (pintype "passive"))
    )
    (net (code "51") (name "/P1 RXIN") (class "Default")
      (node (ref "J2") (pin "8") (pinfunction "RD-_8") (pintype "passive"))
      (node (ref "R60") (pin "2") (pinfunction "2_2") (pintype "passive"))
    )
    (net (code "52") (name "/P1 RXIP") (class "Default")
      (node (ref "J2") (pin "7") (pinfunction "RD+_7") (pintype "passive"))
      (node (ref "R59") (pin "2") (pinfunction "2_2") (pintype "passive"))
    )
    (net (code "53") (name "/P1 SD") (class "Default")
      (node (ref "IC2") (pin "27") (pinfunction "P1_SD_27") (pintype "passive"))
      (node (ref "R35") (pin "2") (pinfunction "2_2") (pintype "passive"))
    )
    (net (code "54") (name "/P1 TXON") (class "Default")
      (node (ref "J2") (pin "2") (pinfunction "TD-_2") (pintype "passive"))
      (node (ref "R58") (pin "2") (pinfunction "2_2") (pintype "passive"))
    )
    (net (code "55") (name "/P1 TXOP") (class "Default")
      (node (ref "J2") (pin "1") (pinfunction "TD+_1") (pintype "passive"))
      (node (ref "R57") (pin "2") (pinfunction "2_2") (pintype "passive"))
    )
    (net (code "56") (name "/PDI EMU") (class "Default")
      (node (ref "IC2") (pin "61") (pinfunction "PDI_EMU_61") (pintype "passive"))
      (node (ref "R4") (pin "2") (pinfunction "2_2") (pintype "passive"))
      (node (ref "R5") (pin "2") (pinfunction "2_2") (pintype "passive"))
    )
    (net (code "57") (name "/SCS ESC") (class "Default")
      (node (ref "C18") (pin "9") (pinfunction "17_9") (pintype "passive"))
      (node (ref "R14") (pin "1") (pinfunction "1_1") (pintype "passive"))
    )
    (net (code "58") (name "/SCS FUNC") (class "Default")
      (node (ref "C18") (pin "10") (pinfunction "18_10") (pintype "passive"))
      (node (ref "R13") (pin "1") (pinfunction "1_1") (pintype "passive"))
    )
    (net (code "59") (name "/SYNC0") (class "Default")
      (node (ref "C19") (pin "16") (pinfunction "2_16") (pintype "passive"))
      (node (ref "R28") (pin "1") (pinfunction "1_1") (pintype "passive"))
    )
    (net (code "60") (name "/SYNC1") (class "Default")
      (node (ref "C19") (pin "2") (pinfunction "3_2") (pintype "passive"))
      (node (ref "R30") (pin "1") (pinfunction "1_1") (pintype "passive"))
    )
    (net (code "61") (name "/TEST") (class "Default")
      (node (ref "IC2") (pin "59") (pinfunction "TEST_59") (pintype "passive"))
      (node (ref "R3") (pin "2") (pinfunction "2_2") (pintype "passive"))
    )
    (net (code "62") (name "GND") (class "Default")
      (node (ref "AMS1") (pin "1") (pinfunction "GND_1") (pintype "passive"))
      (node (ref "C1") (pin "2") (pinfunction "2_2") (pintype "passive"))
      (node (ref "C10") (pin "1") (pinfunction "1_1") (pintype "passive"))
      (node (ref "C11") (pin "1") (pinfunction "1_1") (pintype "passive"))
      (node (ref "C12") (pin "1") (pinfunction "1_1") (pintype "passive"))
      (node (ref "C13") (pin "1") (pinfunction "1_1") (pintype "passive"))
      (node (ref "C14") (pin "1") (pinfunction "1_1") (pintype "passive"))
      (node (ref "C15") (pin "1") (pinfunction "1_1") (pintype "passive"))
      (node (ref "C16") (pin "1") (pinfunction "1_1") (pintype "passive"))
      (node (ref "C17") (pin "7") (pinfunction "12_7") (pintype "passive"))
      (node (ref "C18") (pin "17") (pinfunction "4_17") (pintype "passive"))
      (node (ref "C18") (pin "2") (pinfunction "3_2") (pintype "passive"))
      (node (ref "C19") (pin "8") (pinfunction "15_8") (pintype "passive"))
      (node (ref "C2") (pin "1") (pinfunction "1_1") (pintype "passive"))
      (node (ref "C20") (pin "1") (pinfunction "1_1") (pintype "passive"))
      (node (ref "C21") (pin "1") (pinfunction "1_1") (pintype "passive"))
      (node (ref "C22") (pin "1") (pinfunction "1_1") (pintype "passive"))
      (node (ref "C23") (pin "1") (pinfunction "1_1") (pintype "passive"))
      (node (ref "C24") (pin "1") (pinfunction "1_1") (pintype "passive"))
      (node (ref "C25") (pin "1") (pinfunction "1_1") (pintype "passive"))
      (node (ref "C26") (pin "1") (pinfunction "1_1") (pintype "passive"))
      (node (ref "C27") (pin "2") (pinfunction "2_2") (pintype "passive"))
      (node (ref "C28") (pin "2") (pinfunction "2_2") (pintype "passive"))
      (node (ref "C29") (pin "2") (pinfunction "2_2") (pintype "passive"))
      (node (ref "C3") (pin "1") (pinfunction "1_1") (pintype "passive"))
      (node (ref "C30") (pin "2") (pinfunction "2_2") (pintype "passive"))
      (node (ref "C4") (pin "1") (pinfunction "1_1") (pintype "passive"))
      (node (ref "C5") (pin "1") (pinfunction "1_1") (pintype "passive"))
      (node (ref "C6") (pin "1") (pinfunction "1_1") (pintype "passive"))
      (node (ref "C7") (pin "1") (pinfunction "1_1") (pintype "passive"))
      (node (ref "C8") (pin "1") (pinfunction "1_1") (pintype "passive"))
      (node (ref "C9") (pin "1") (pinfunction "1_1") (pintype "passive"))
      (node (ref "D2") (pin "2") (pinfunction "K_2") (pintype "passive"))
      (node (ref "D3") (pin "2") (pinfunction "K_2") (pintype "passive"))
      (node (ref "IC1") (pin "1") (pinfunction "A0_1") (pintype "passive"))
      (node (ref "IC1") (pin "2") (pinfunction "A1_2") (pintype "passive"))
      (node (ref "IC1") (pin "3") (pinfunction "A2_3") (pintype "passive"))
      (node (ref "IC1") (pin "4") (pinfunction "GND_4") (pintype "passive"))
      (node (ref "IC2") (pin "56") (pinfunction "NC_56") (pintype "passive"))
      (node (ref "IC2") (pin "81") (pinfunction "EP_81") (pintype "passive"))
      (node (ref "J1") (pin "11") (pinfunction "C1_11") (pintype "passive"))
      (node (ref "J1") (pin "13") (pinfunction "S1_13") (pintype "passive"))
      (node (ref "J1") (pin "14") (pinfunction "S2_14") (pintype "passive"))
      (node (ref "J1") (pin "4") (pinfunction "CHS_GND_4") (pintype "passive"))
      (node (ref "J1") (pin "5") (pinfunction "CHS_GND_5") (pintype "passive"))
      (node (ref "J2") (pin "11") (pinfunction "C1_11") (pintype "passive"))
      (node (ref "J2") (pin "13") (pinfunction "S1_13") (pintype "passive"))
      (node (ref "J2") (pin "14") (pinfunction "S2_14") (pintype "passive"))
      (node (ref "J2") (pin "4") (pinfunction "CHS_GND_4") (pintype "passive"))
      (node (ref "J2") (pin "5") (pinfunction "CHS_GND_5") (pintype "passive"))
      (node (ref "R23") (pin "1") (pinfunction "1_1") (pintype "passive"))
      (node (ref "R24") (pin "1") (pinfunction "1_1") (pintype "passive"))
      (node (ref "R25") (pin "1") (pinfunction "1_1") (pintype "passive"))
      (node (ref "R29") (pin "1") (pinfunction "1_1") (pintype "passive"))
      (node (ref "R3") (pin "1") (pinfunction "1_1") (pintype "passive"))
      (node (ref "R35") (pin "1") (pinfunction "1_1") (pintype "passive"))
      (node (ref "R5") (pin "1") (pinfunction "1_1") (pintype "passive"))
      (node (ref "R61") (pin "2") (pinfunction "2_2") (pintype "passive"))
      (node (ref "R7") (pin "2") (pinfunction "2_2") (pintype "passive"))
    )
    (net (code "63") (name "Net-(C27-Pad1)") (class "Default")
      (node (ref "C27") (pin "1") (pinfunction "1_1") (pintype "passive"))
      (node (ref "R66") (pin "1") (pinfunction "1_1") (pintype "passive"))
    )
    (net (code "64") (name "Net-(C28-Pad1)") (class "Default")
      (node (ref "C28") (pin "1") (pinfunction "1_1") (pintype "passive"))
      (node (ref "R67") (pin "1") (pinfunction "1_1") (pintype "passive"))
    )
    (net (code "65") (name "Net-(C29-Pad1)") (class "Default")
      (node (ref "C29") (pin "1") (pinfunction "1_1") (pintype "passive"))
      (node (ref "R68") (pin "1") (pinfunction "1_1") (pintype "passive"))
    )
    (net (code "66") (name "Net-(C30-Pad1)") (class "Default")
      (node (ref "C30") (pin "1") (pinfunction "1_1") (pintype "passive"))
      (node (ref "R69") (pin "1") (pinfunction "1_1") (pintype "passive"))
    )
    (net (code "67") (name "Net-(D1-K)") (class "Default")
      (node (ref "D1") (pin "2") (pinfunction "K_2") (pintype "passive"))
      (node (ref "R21") (pin "1") (pinfunction "1_1") (pintype "passive"))
    )
    (net (code "68") (name "Net-(D2-A)") (class "Default")
      (node (ref "D2") (pin "1") (pinfunction "A_1") (pintype "passive"))
      (node (ref "R55") (pin "1") (pinfunction "1_1") (pintype "passive"))
    )
    (net (code "69") (name "Net-(D3-A)") (class "Default")
      (node (ref "D3") (pin "1") (pinfunction "A_1") (pintype "passive"))
      (node (ref "R56") (pin "1") (pinfunction "1_1") (pintype "passive"))
    )
    (net (code "70") (name "Net-(IC2-EOF_{slash}_LFCSN_{slash}_SCS_FUNC)") (class "Default")
      (node (ref "IC2") (pin "80") (pinfunction "EOF_/_LFCSN_/_SCS_FUNC_80") (pintype "passive"))
      (node (ref "R13") (pin "2") (pinfunction "2_2") (pintype "passive"))
    )
    (net (code "71") (name "Net-(IC2-IO[0]_{slash}_LDA[0]_{slash}_MSCLK)") (class "Default")
      (node (ref "IC2") (pin "43") (pinfunction "IO[0]_/_LDA[0]_/_MSCLK_43") (pintype "passive"))
      (node (ref "R53") (pin "1") (pinfunction "1_1") (pintype "passive"))
    )
    (net (code "72") (name "Net-(IC2-IO[1]_{slash}_LDA[1]_{slash}_MMOSI)") (class "Default")
      (node (ref "IC2") (pin "47") (pinfunction "IO[1]_/_LDA[1]_/_MMOSI_47") (pintype "passive"))
      (node (ref "R48") (pin "1") (pinfunction "1_1") (pintype "passive"))
    )
    (net (code "73") (name "Net-(IC2-IO[2]_{slash}_LDA[2]_{slash}_MMISO)") (class "Default")
      (node (ref "IC2") (pin "4") (pinfunction "IO[2]_/_LDA[2]_/_MMISO_4") (pintype "passive"))
      (node (ref "R31") (pin "2") (pinfunction "2_2") (pintype "passive"))
    )
    (net (code "74") (name "Net-(IC2-IO[3]_{slash}_LDA[3]_{slash}_MINT)") (class "Default")
      (node (ref "IC2") (pin "51") (pinfunction "IO[3]_/_LDA[3]_/_MINT_51") (pintype "passive"))
      (node (ref "R40") (pin "1") (pinfunction "1_1") (pintype "passive"))
    )
    (net (code "75") (name "Net-(IC2-IO[4]_{slash}_LDA[4]_{slash}_MSS[0])") (class "Default")
      (node (ref "IC2") (pin "60") (pinfunction "IO[4]_/_LDA[4]_/_MSS[0]_60") (pintype "passive"))
      (node (ref "R27") (pin "1") (pinfunction "1_1") (pintype "passive"))
    )
    (net (code "76") (name "Net-(IC2-IO[5]_{slash}_LDA[5]_{slash}_MSS[1])") (class "Default")
      (node (ref "IC2") (pin "53") (pinfunction "IO[5]_/_LDA[5]_/_MSS[1]_53") (pintype "passive"))
      (node (ref "R37") (pin "1") (pinfunction "1_1") (pintype "passive"))
    )
    (net (code "77") (name "Net-(IC2-IO[6]_{slash}_LDA[6]_{slash}_MSS[2])") (class "Default")
      (node (ref "IC2") (pin "67") (pinfunction "IO[6]_/_LDA[6]_/_MSS[2]_67") (pintype "passive"))
      (node (ref "R8") (pin "1") (pinfunction "1_1") (pintype "passive"))
    )
    (net (code "78") (name "Net-(IC2-IO[7]_{slash}_LDA[7]_{slash}_MSS[3])") (class "Default")
      (node (ref "IC2") (pin "69") (pinfunction "IO[7]_/_LDA[7]_/_MSS[3]_69") (pintype "passive"))
      (node (ref "R6") (pin "1") (pinfunction "1_1") (pintype "passive"))
    )
    (net (code "79") (name "Net-(IC2-IO[8]_{slash}_LA[0]_{slash}_MDRLD)") (class "Default")
      (node (ref "IC2") (pin "71") (pinfunction "IO[8]_/_LA[0]_/_MDRLD_71") (pintype "passive"))
      (node (ref "R20") (pin "1") (pinfunction "1_1") (pintype "passive"))
    )
    (net (code "80") (name "Net-(IC2-IO[9]_{slash}_LA[1]_{slash}_MTRG)") (class "Default")
      (node (ref "IC2") (pin "74") (pinfunction "IO[9]_/_LA[1]_/_MTRG_74") (pintype "passive"))
      (node (ref "R18") (pin "1") (pinfunction "1_1") (pintype "passive"))
    )
    (net (code "81") (name "Net-(IC2-IO[10]_{slash}_LA[2]_{slash}_SFINT)") (class "Default")
      (node (ref "IC2") (pin "49") (pinfunction "IO[10]_/_LA[2]_/_SFINT_49") (pintype "passive"))
      (node (ref "R44") (pin "1") (pinfunction "1_1") (pintype "passive"))
    )
    (net (code "82") (name "Net-(IC2-IO[11]_{slash}_LA[3]_{slash}_FMISO)") (class "Default")
      (node (ref "IC2") (pin "7") (pinfunction "IO[11]_/_LA[3]_/_FMISO_7") (pintype "passive"))
      (node (ref "R34") (pin "2") (pinfunction "2_2") (pintype "passive"))
    )
    (net (code "83") (name "Net-(IC2-IO[12]_{slash}_LA[4]_{slash}_FSCLK)") (class "Default")
      (node (ref "IC2") (pin "9") (pinfunction "IO[12]_/_LA[4]_/_FSCLK_9") (pintype "passive"))
      (node (ref "R38") (pin "2") (pinfunction "2_2") (pintype "passive"))
    )
    (net (code "84") (name "Net-(IC2-IO[13]_{slash}_LA[5]_{slash}_SMOSI)") (class "Default")
      (node (ref "IC2") (pin "12") (pinfunction "IO[13]_/_LA[5]_/_SMOSI_12") (pintype "passive"))
      (node (ref "R43") (pin "2") (pinfunction "2_2") (pintype "passive"))
    )
    (net (code "85") (name "Net-(IC2-IO[14]_{slash}_LA[6])") (class "Default")
      (node (ref "IC2") (pin "14") (pinfunction "IO[14]_/_LA[6]_14") (pintype "passive"))
      (node (ref "R47") (pin "2") (pinfunction "2_2") (pintype "passive"))
    )
    (net (code "86") (name "Net-(IC2-IO[15]_{slash}_LA[7])") (class "Default")
      (node (ref "IC2") (pin "17") (pinfunction "IO[15]_/_LA[7]_17") (pintype "passive"))
      (node (ref "R50") (pin "2") (pinfunction "2_2") (pintype "passive"))
    )
    (net (code "87") (name "Net-(IC2-IO[16]_{slash}_LA[8]_{slash}_LINK)") (class "Default")
      (node (ref "IC2") (pin "44") (pinfunction "IO[16]_/_LA[8]_/_LINK_44") (pintype "passive"))
      (node (ref "R51") (pin "1") (pinfunction "1_1") (pintype "passive"))
    )
    (net (code "88") (name "Net-(IC2-IO[17]_{slash}_LA[9]_{slash}_PULAB_{slash}_MDIO)") (class "Default")
      (node (ref "IC2") (pin "48") (pinfunction "IO[17]_/_LA[9]_/_PULAB_/_MDIO_48") (pintype "passive"))
      (node (ref "R46") (pin "1") (pinfunction "1_1") (pintype "passive"))
    )
    (net (code "89") (name "Net-(IC2-IO[18]_{slash}_LA[10]_{slash}_PULC_{slash}_MDC)") (class "Default")
      (node (ref "IC2") (pin "50") (pinfunction "IO[18]_/_LA[10]_/_PULC_/_MDC_50") (pintype "passive"))
      (node (ref "R42") (pin "1") (pinfunction "1_1") (pintype "passive"))
    )
    (net (code "90") (name "Net-(IC2-IO[19]_{slash}_LA[11]_{slash}_PULZ_{slash}_TXD[0])") (class "Default")
      (node (ref "IC2") (pin "52") (pinfunction "IO[19]_/_LA[11]_/_PULZ_/_TXD[0]_52") (pintype "passive"))
      (node (ref "R39") (pin "1") (pinfunction "1_1") (pintype "passive"))
    )
    (net (code "91") (name "Net-(IC2-IO[20]_{slash}_LA[12]_{slash}_PULB_{slash}_TXD[1])") (class "Default")
      (node (ref "IC2") (pin "42") (pinfunction "IO[20]_/_LA[12]_/_PULB_/_TXD[1]_42") (pintype "passive"))
      (node (ref "R54") (pin "1") (pinfunction "1_1") (pintype "passive"))
    )
    (net (code "92") (name "Net-(IC2-IO[21]_{slash}_LA[13]_{slash}_PULA_{slash}_TXD[2])") (class "Default")
      (node (ref "IC2") (pin "66") (pinfunction "IO[21]_/_LA[13]_/_PULA_/_TXD[2]_66") (pintype "passive"))
      (node (ref "R9") (pin "2") (pinfunction "2_2") (pintype "passive"))
    )
    (net (code "93") (name "Net-(IC2-IO[22]_{slash}_LBHE_{slash}_PWM3H_{slash}_TXD[3])") (class "Default")
      (node (ref "IC2") (pin "68") (pinfunction "IO[22]_/_LBHE_/_PWM3H_/_TXD[3]_68") (pintype "passive"))
      (node (ref "R7") (pin "1") (pinfunction "1_1") (pintype "passive"))
    )
    (net (code "94") (name "Net-(IC2-IO[24]_{slash}_LDA[8]_{slash}_PWM2H_{slash}_RXD[0])") (class "Default")
      (node (ref "IC2") (pin "73") (pinfunction "IO[24]_/_LDA[8]_/_PWM2H_/_RXD[0]_73") (pintype "passive"))
      (node (ref "R19") (pin "2") (pinfunction "2_2") (pintype "passive"))
    )
    (net (code "95") (name "Net-(IC2-IO[25]_{slash}_LDA[9]_{slash}_PWM2L_{slash}_RXD[1])") (class "Default")
      (node (ref "IC2") (pin "75") (pinfunction "IO[25]_/_LDA[9]_/_PWM2L_/_RXD[1]_75") (pintype "passive"))
      (node (ref "R17") (pin "2") (pinfunction "2_2") (pintype "passive"))
    )
    (net (code "96") (name "Net-(IC2-IO[26]_{slash}_LDA[10]_{slash}_PWM1H_{slash}_RXD[2])") (class "Default")
      (node (ref "IC2") (pin "76") (pinfunction "IO[26]_/_LDA[10]_/_PWM1H_/_RXD[2]_76") (pintype "passive"))
      (node (ref "R16") (pin "2") (pinfunction "2_2") (pintype "passive"))
    )
    (net (code "97") (name "Net-(IC2-IO[27]_{slash}_LDA[11]_{slash}_PWM1L_{slash}_RXD[3])") (class "Default")
      (node (ref "IC2") (pin "8") (pinfunction "IO[27]_/_LDA[11]_/_PWM1L_/_RXD[3]_8") (pintype "passive"))
      (node (ref "R36") (pin "2") (pinfunction "2_2") (pintype "passive"))
    )
    (net (code "98") (name "Net-(IC2-IO[28]_{slash}_LDA[12]_{slash}_EMN_{slash}_RX_ER)") (class "Default")
      (node (ref "IC2") (pin "11") (pinfunction "IO[28]_/_LDA[12]_/_EMN_/_RX_ER_11") (pintype "passive"))
      (node (ref "R41") (pin "2") (pinfunction "2_2") (pintype "passive"))
    )
    (net (code "99") (name "Net-(IC2-IO[29]_{slash}_LDA[13]_{slash}_ENCA_{slash}_RX_DV)") (class "Default")
      (node (ref "IC2") (pin "13") (pinfunction "IO[29]_/_LDA[13]_/_ENCA_/_RX_DV_13") (pintype "passive"))
      (node (ref "R45") (pin "2") (pinfunction "2_2") (pintype "passive"))
    )
    (net (code "100") (name "Net-(IC2-IO[30]_{slash}_LDA[14]_{slash}_ENCB_{slash}_RX_CLK)") (class "Default")
      (node (ref "IC2") (pin "15") (pinfunction "IO[30]_/_LDA[14]_/_ENCB_/_RX_CLK_15") (pintype "passive"))
      (node (ref "R49") (pin "2") (pinfunction "2_2") (pintype "passive"))
    )
    (net (code "101") (name "Net-(IC2-IO[31]_{slash}_LDA[15]_{slash}_ENCZ_{slash}_MCLK)") (class "Default")
      (node (ref "IC2") (pin "18") (pinfunction "IO[31]_/_LDA[15]_/_ENCZ_/_MCLK_18") (pintype "passive"))
      (node (ref "R52") (pin "2") (pinfunction "2_2") (pintype "passive"))
    )
    (net (code "102") (name "Net-(IC2-LAT_IN_{slash}_LRDY_{slash}_MISO)") (class "Default")
      (node (ref "IC2") (pin "6") (pinfunction "LAT_IN_/_LRDY_/_MISO_6") (pintype "passive"))
      (node (ref "R33") (pin "2") (pinfunction "2_2") (pintype "passive"))
    )
    (net (code "103") (name "Net-(IC2-OE_EXT_{slash}_LRDN_{slash}_SCLK)") (class "Default")
      (node (ref "IC2") (pin "64") (pinfunction "OE_EXT_/_LRDN_/_SCLK_64") (pintype "passive"))
      (node (ref "R10") (pin "2") (pinfunction "2_2") (pintype "passive"))
    )
    (net (code "104") (name "Net-(IC2-OUTVLD_{slash}_LWRN_{slash}_MOSI)") (class "Default")
      (node (ref "IC2") (pin "78") (pinfunction "OUTVLD_/_LWRN_/_MOSI_78") (pintype "passive"))
      (node (ref "R15") (pin "2") (pinfunction "2_2") (pintype "passive"))
    )
    (net (code "105") (name "Net-(IC2-P0_RXIN)") (class "Default")
      (node (ref "IC2") (pin "35") (pinfunction "P0_RXIN_35") (pintype "passive"))
      (node (ref "R62") (pin "1") (pinfunction "1_1") (pintype "passive"))
    )
    (net (code "106") (name "Net-(IC2-P0_RXIP)") (class "Default")
      (node (ref "IC2") (pin "36") (pinfunction "P0_RXIP_36") (pintype "passive"))
      (node (ref "R63") (pin "1") (pinfunction "1_1") (pintype "passive"))
    )
    (net (code "107") (name "Net-(IC2-P0_TXON)") (class "Default")
      (node (ref "IC2") (pin "37") (pinfunction "P0_TXON_37") (pintype "passive"))
      (node (ref "R64") (pin "1") (pinfunction "1_1") (pintype "passive"))
    )
    (net (code "108") (name "Net-(IC2-P0_TXOP)") (class "Default")
      (node (ref "IC2") (pin "38") (pinfunction "P0_TXOP_38") (pintype "passive"))
      (node (ref "R65") (pin "1") (pinfunction "1_1") (pintype "passive"))
    )
    (net (code "109") (name "Net-(IC2-P1_RXIN)") (class "Default")
      (node (ref "IC2") (pin "26") (pinfunction "P1_RXIN_26") (pintype "passive"))
      (node (ref "R60") (pin "1") (pinfunction "1_1") (pintype "passive"))
    )
    (net (code "110") (name "Net-(IC2-P1_RXIP)") (class "Default")
      (node (ref "IC2") (pin "25") (pinfunction "P1_RXIP_25") (pintype "passive"))
      (node (ref "R59") (pin "1") (pinfunction "1_1") (pintype "passive"))
    )
    (net (code "111") (name "Net-(IC2-P1_TXON)") (class "Default")
      (node (ref "IC2") (pin "24") (pinfunction "P1_TXON_24") (pintype "passive"))
      (node (ref "R58") (pin "1") (pinfunction "1_1") (pintype "passive"))
    )
    (net (code "112") (name "Net-(IC2-P1_TXOP)") (class "Default")
      (node (ref "IC2") (pin "23") (pinfunction "P1_TXOP_23") (pintype "passive"))
      (node (ref "R57") (pin "1") (pinfunction "1_1") (pintype "passive"))
    )
    (net (code "113") (name "Net-(IC2-RSET_BG)") (class "Default")
      (node (ref "IC2") (pin "33") (pinfunction "RSET_BG_33") (pintype "passive"))
      (node (ref "R61") (pin "1") (pinfunction "1_1") (pintype "passive"))
    )
    (net (code "114") (name "Net-(IC2-RSTN)") (class "Default")
      (node (ref "C20") (pin "2") (pinfunction "2_2") (pintype "passive"))
      (node (ref "IC2") (pin "57") (pinfunction "RSTN_57") (pintype "passive"))
      (node (ref "R32") (pin "1") (pinfunction "1_1") (pintype "passive"))
    )
    (net (code "115") (name "Net-(IC2-SCL)") (class "Default")
      (node (ref "IC2") (pin "62") (pinfunction "SCL_62") (pintype "passive"))
      (node (ref "R12") (pin "2") (pinfunction "2_2") (pintype "passive"))
    )
    (net (code "116") (name "Net-(IC2-SDA)") (class "Default")
      (node (ref "IC2") (pin "63") (pinfunction "SDA_63") (pintype "passive"))
      (node (ref "R11") (pin "2") (pinfunction "2_2") (pintype "passive"))
    )
    (net (code "117") (name "Net-(IC2-SOF_{slash}_LECSN_{slash}_SCS_ESC)") (class "Default")
      (node (ref "IC2") (pin "79") (pinfunction "SOF_/_LECSN_/_SCS_ESC_79") (pintype "passive"))
      (node (ref "R14") (pin "2") (pinfunction "2_2") (pintype "passive"))
    )
    (net (code "118") (name "Net-(IC2-SYNC_LATCH[0])") (class "Default")
      (node (ref "IC2") (pin "2") (pinfunction "SYNC_LATCH[0]_2") (pintype "passive"))
      (node (ref "R28") (pin "2") (pinfunction "2_2") (pintype "passive"))
    )
    (net (code "119") (name "Net-(IC2-SYNC_LATCH[1])") (class "Default")
      (node (ref "IC2") (pin "3") (pinfunction "SYNC_LATCH[1]_3") (pintype "passive"))
      (node (ref "R30") (pin "2") (pinfunction "2_2") (pintype "passive"))
    )
    (net (code "120") (name "Net-(IC2-WD_TRIG_{slash}_LINT_{slash}_SINT)") (class "Default")
      (node (ref "IC2") (pin "1") (pinfunction "WD_TRIG_/_LINT_/_SINT_1") (pintype "passive"))
      (node (ref "R26") (pin "2") (pinfunction "2_2") (pintype "passive"))
    )
    (net (code "121") (name "Net-(IC2-XSCI)") (class "Default")
      (node (ref "C22") (pin "2") (pinfunction "2_2") (pintype "passive"))
      (node (ref "IC2") (pin "31") (pinfunction "XSCI_31") (pintype "passive"))
      (node (ref "X1") (pin "1") (pinfunction "1_1") (pintype "passive"))
    )
    (net (code "122") (name "Net-(IC2-XSCO)") (class "Default")
      (node (ref "C21") (pin "2") (pinfunction "2_2") (pintype "passive"))
      (node (ref "IC2") (pin "30") (pinfunction "XSCO_30") (pintype "passive"))
      (node (ref "X1") (pin "2") (pinfunction "2_2") (pintype "passive"))
    )
    (net (code "123") (name "Net-(J1-A)") (class "Default")
      (node (ref "J1") (pin "9") (pinfunction "A_9") (pintype "passive"))
      (node (ref "R70") (pin "2") (pinfunction "2_2") (pintype "passive"))
    )
    (net (code "124") (name "Net-(J1-A1)") (class "Default")
      (node (ref "J1") (pin "12") (pinfunction "A1_12") (pintype "passive"))
      (node (ref "R72") (pin "2") (pinfunction "2_2") (pintype "passive"))
    )
    (net (code "125") (name "Net-(J1-RD+-Pad3)") (class "Default")
      (node (ref "J1") (pin "3") (pinfunction "RD+_3") (pintype "passive"))
      (node (ref "R66") (pin "2") (pinfunction "2_2") (pintype "passive"))
    )
    (net (code "126") (name "Net-(J1-RXCT)") (class "Default")
      (node (ref "J1") (pin "6") (pinfunction "RXCT_6") (pintype "passive"))
      (node (ref "R68") (pin "2") (pinfunction "2_2") (pintype "passive"))
    )
    (net (code "127") (name "Net-(J2-A)") (class "Default")
      (node (ref "J2") (pin "9") (pinfunction "A_9") (pintype "passive"))
      (node (ref "R71") (pin "2") (pinfunction "2_2") (pintype "passive"))
    )
    (net (code "128") (name "Net-(J2-A1)") (class "Default")
      (node (ref "J2") (pin "12") (pinfunction "A1_12") (pintype "passive"))
      (node (ref "R73") (pin "2") (pinfunction "2_2") (pintype "passive"))
    )
    (net (code "129") (name "Net-(J2-RD+-Pad3)") (class "Default")
      (node (ref "J2") (pin "3") (pinfunction "RD+_3") (pintype "passive"))
      (node (ref "R67") (pin "2") (pinfunction "2_2") (pintype "passive"))
    )
    (net (code "130") (name "Net-(J2-RXCT)") (class "Default")
      (node (ref "J2") (pin "6") (pinfunction "RXCT_6") (pintype "passive"))
      (node (ref "R69") (pin "2") (pinfunction "2_2") (pintype "passive"))
    )
    (net (code "131") (name "unconnected-(IC1-VCC-Pad8)") (class "Default")
      (node (ref "IC1") (pin "8") (pinfunction "VCC_8") (pintype "passive"))
    )
    (net (code "132") (name "unconnected-(IC1-WP-Pad7)") (class "Default")
      (node (ref "IC1") (pin "7") (pinfunction "WP_7") (pintype "passive"))
    )
    (net (code "133") (name "unconnected-(IC2-IO[23]_{slash}_PWM3L_{slash}_TX_EN-Pad70)") (class "Default")
      (node (ref "IC2") (pin "70") (pinfunction "IO[23]_/_PWM3L_/_TX_EN_70") (pintype "passive"))
    )
    (net (code "134") (name "unconnected-(IC2-RSTO-Pad58)") (class "Default")
      (node (ref "IC2") (pin "58") (pinfunction "RSTO_58") (pintype "passive"))
    )
    (net (code "135") (name "unconnected-(J1-C-Pad10)") (class "Default")
      (node (ref "J1") (pin "10") (pinfunction "C_10") (pintype "passive"))
    )
    (net (code "136") (name "unconnected-(J2-C-Pad10)") (class "Default")
      (node (ref "J2") (pin "10") (pinfunction "C_10") (pintype "passive"))
    )
  )
)
